# pot.net
KiCad netlist of a schematic drawn in EAGLE
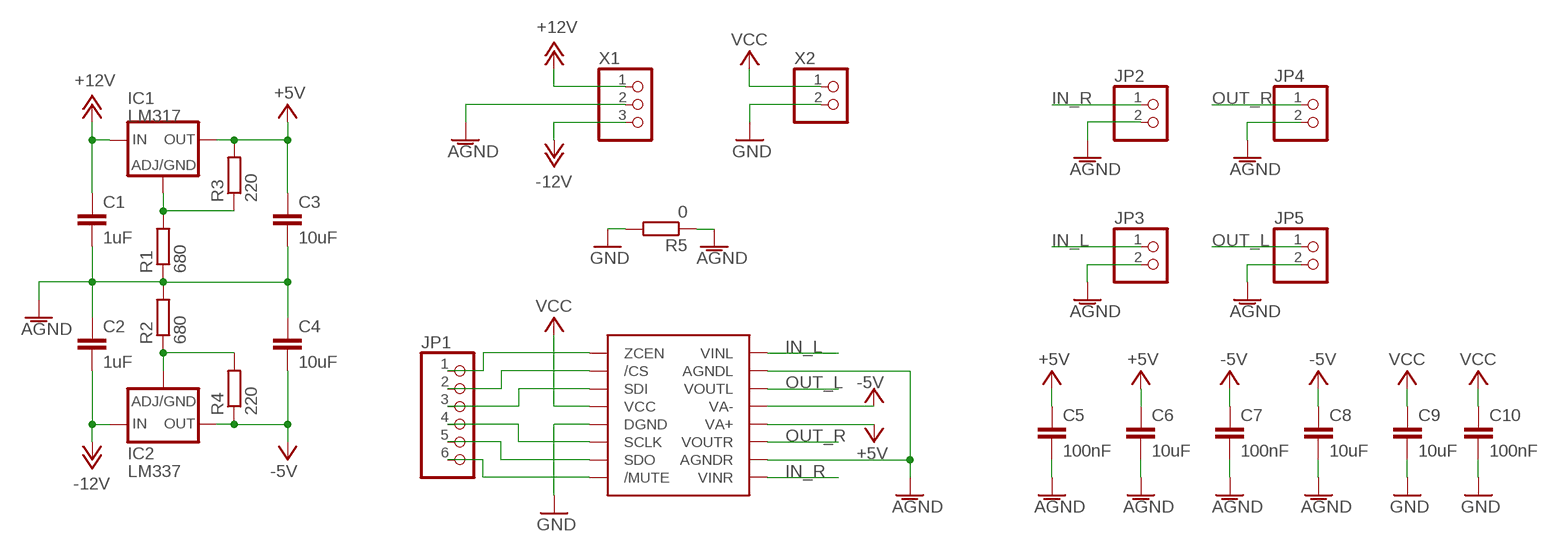
[diagram p0: schematic, sheet 1]

(export (version "E")
  (design (tool "Eeschema 10.0.6"))
  (components
    (comp (ref "C1")
      (value "1uF")
      (footprint "eagle-import:C0805K")
      (libsource (lib "eagle-import") (part "C-EUC0805K"))
    )
    (comp (ref "C2")
      (value "1uF")
      (footprint "eagle-import:C0805K")
      (libsource (lib "eagle-import") (part "C-EUC0805K"))
    )
    (comp (ref "C3")
      (value "10uF")
      (footprint "eagle-import:C0805K")
      (libsource (lib "eagle-import") (part "C-EUC0805K"))
    )
    (comp (ref "C4")
      (value "10uF")
      (footprint "eagle-import:C0805K")
      (libsource (lib "eagle-import") (part "C-EUC0805K"))
    )
    (comp (ref "C5")
      (value "100nF")
      (footprint "eagle-import:C0805K")
      (libsource (lib "eagle-import") (part "C-EUC0805K"))
    )
    (comp (ref "C6")
      (value "10uF")
      (footprint "eagle-import:C0805K")
      (libsource (lib "eagle-import") (part "C-EUC0805K"))
    )
    (comp (ref "C7")
      (value "100nF")
      (footprint "eagle-import:C0805K")
      (libsource (lib "eagle-import") (part "C-EUC0805K"))
    )
    (comp (ref "C8")
      (value "10uF")
      (footprint "eagle-import:C0805K")
      (libsource (lib "eagle-import") (part "C-EUC0805K"))
    )
    (comp (ref "C9")
      (value "10uF")
      (footprint "eagle-import:C0805K")
      (libsource (lib "eagle-import") (part "C-EUC0805K"))
    )
    (comp (ref "C10")
      (value "100nF")
      (footprint "eagle-import:C0805K")
      (libsource (lib "eagle-import") (part "C-EUC0805K"))
    )
    (comp (ref "IC1")
      (value "LM317")
      (footprint "eagle-import:SOT223")
      (libsource (lib "eagle-import") (part "LM317"))
    )
    (comp (ref "IC2")
      (value "LM337")
      (footprint "eagle-import:SOT223")
      (libsource (lib "eagle-import") (part "LM337"))
    )
    (comp (ref "JP1")
      (value "PINHD-1X6")
      (footprint "eagle-import:1X06")
      (libsource (lib "eagle-import") (part "PINHD-1X6"))
    )
    (comp (ref "JP2")
      (value "PINHD-1X2")
      (footprint "eagle-import:1X02")
      (libsource (lib "eagle-import") (part "PINHD-1X2"))
    )
    (comp (ref "JP3")
      (value "PINHD-1X2")
      (footprint "eagle-import:1X02")
      (libsource (lib "eagle-import") (part "PINHD-1X2"))
    )
    (comp (ref "JP4")
      (value "PINHD-1X2")
      (footprint "eagle-import:1X02")
      (libsource (lib "eagle-import") (part "PINHD-1X2"))
    )
    (comp (ref "JP5")
      (value "PINHD-1X2")
      (footprint "eagle-import:1X02")
      (libsource (lib "eagle-import") (part "PINHD-1X2"))
    )
    (comp (ref "R1")
      (value "680")
      (footprint "eagle-import:R0805")
      (libsource (lib "eagle-import") (part "R-EU_"))
    )
    (comp (ref "R2")
      (value "680")
      (footprint "eagle-import:R0805")
      (libsource (lib "eagle-import") (part "R-EU_"))
    )
    (comp (ref "R3")
      (value "220")
      (footprint "eagle-import:R0805")
      (libsource (lib "eagle-import") (part "R-EU_"))
    )
    (comp (ref "R4")
      (value "220")
      (footprint "eagle-import:R0805")
      (libsource (lib "eagle-import") (part "R-EU_"))
    )
    (comp (ref "R5")
      (value "0")
      (footprint "eagle-import:R0805")
      (libsource (lib "eagle-import") (part "R-EU_"))
    )
    (comp (ref "U1")
      (value "PGA2311")
      (footprint "eagle-import:SO16W")
      (libsource (lib "eagle-import") (part "PGA2311"))
    )
    (comp (ref "X1")
      (value "22-23-2031")
      (footprint "eagle-import:22-23-2031")
      (libsource (lib "eagle-import") (part "22-23-2031"))
    )
    (comp (ref "X2")
      (value "22-23-2021")
      (footprint "eagle-import:22-23-2021")
      (libsource (lib "eagle-import") (part "22-23-2021"))
    )
  )
  (nets
    (net (code "1") (name "+5V") (class "Default")
      (node (ref "C3") (pin "1") (pinfunction "1_1") (pintype "passive"))
      (node (ref "C5") (pin "1") (pinfunction "1_1") (pintype "passive"))
      (node (ref "C6") (pin "1") (pinfunction "1_1") (pintype "passive"))
      (node (ref "IC1") (pin "2") (pinfunction "OUT_2") (pintype "passive"))
      (node (ref "IC1") (pin "4") (pinfunction "OUT_4") (pintype "passive"))
      (node (ref "R3") (pin "2") (pinfunction "2_2") (pintype "passive"))
      (node (ref "U1") (pin "12") (pinfunction "VA+_12") (pintype "bidirectional"))
    )
    (net (code "2") (name "+12V") (class "Default")
      (node (ref "C1") (pin "1") (pinfunction "1_1") (pintype "passive"))
      (node (ref "IC1") (pin "3") (pinfunction "IN_3") (pintype "input"))
      (node (ref "X1") (pin "1") (pinfunction "1_1") (pintype "passive"))
    )
    (net (code "3") (name "-5V") (class "Default")
      (node (ref "C4") (pin "1") (pinfunction "1_1") (pintype "passive"))
      (node (ref "C7") (pin "1") (pinfunction "1_1") (pintype "passive"))
      (node (ref "C8") (pin "1") (pinfunction "1_1") (pintype "passive"))
      (node (ref "IC2") (pin "3") (pinfunction "OUT_3") (pintype "passive"))
      (node (ref "R4") (pin "1") (pinfunction "1_1") (pintype "passive"))
      (node (ref "U1") (pin "13") (pinfunction "VA-_13") (pintype "bidirectional"))
    )
    (net (code "4") (name "-12V") (class "Default")
      (node (ref "C2") (pin "1") (pinfunction "1_1") (pintype "passive"))
      (node (ref "IC2") (pin "2") (pinfunction "IN_2") (pintype "input"))
      (node (ref "IC2") (pin "4") (pinfunction "IN_4") (pintype "input"))
      (node (ref "X1") (pin "3") (pinfunction "3_3") (pintype "passive"))
    )
    (net (code "5") (name "/IN_L") (class "Default")
      (node (ref "JP3") (pin "1") (pinfunction "1_1") (pintype "passive"))
      (node (ref "U1") (pin "16") (pinfunction "VINL_16") (pintype "bidirectional"))
    )
    (net (code "6") (name "/IN_R") (class "Default")
      (node (ref "JP2") (pin "1") (pinfunction "1_1") (pintype "passive"))
      (node (ref "U1") (pin "9") (pinfunction "VINR_9") (pintype "bidirectional"))
    )
    (net (code "7") (name "/OUT_L") (class "Default")
      (node (ref "JP5") (pin "1") (pinfunction "1_1") (pintype "passive"))
      (node (ref "U1") (pin "14") (pinfunction "VOUTL_14") (pintype "bidirectional"))
    )
    (net (code "8") (name "/OUT_R") (class "Default")
      (node (ref "JP4") (pin "1") (pinfunction "1_1") (pintype "passive"))
      (node (ref "U1") (pin "11") (pinfunction "VOUTR_11") (pintype "bidirectional"))
    )
    (net (code "9") (name "AGND") (class "Default")
      (node (ref "C1") (pin "2") (pinfunction "2_2") (pintype "passive"))
      (node (ref "C2") (pin "2") (pinfunction "2_2") (pintype "passive"))
      (node (ref "C3") (pin "2") (pinfunction "2_2") (pintype "passive"))
      (node (ref "C4") (pin "2") (pinfunction "2_2") (pintype "passive"))
      (node (ref "C5") (pin "2") (pinfunction "2_2") (pintype "passive"))
      (node (ref "C6") (pin "2") (pinfunction "2_2") (pintype "passive"))
      (node (ref "C7") (pin "2") (pinfunction "2_2") (pintype "passive"))
      (node (ref "C8") (pin "2") (pinfunction "2_2") (pintype "passive"))
      (node (ref "JP2") (pin "2") (pinfunction "2_2") (pintype "passive"))
      (node (ref "JP3") (pin "2") (pinfunction "2_2") (pintype "passive"))
      (node (ref "JP4") (pin "2") (pinfunction "2_2") (pintype "passive"))
      (node (ref "JP5") (pin "2") (pinfunction "2_2") (pintype "passive"))
      (node (ref "R1") (pin "1") (pinfunction "1_1") (pintype "passive"))
      (node (ref "R2") (pin "2") (pinfunction "2_2") (pintype "passive"))
      (node (ref "R5") (pin "1") (pinfunction "1_1") (pintype "passive"))
      (node (ref "U1") (pin "10") (pinfunction "AGNDR_10") (pintype "bidirectional"))
      (node (ref "U1") (pin "15") (pinfunction "AGNDL_15") (pintype "bidirectional"))
      (node (ref "X1") (pin "2") (pinfunction "2_2") (pintype "passive"))
    )
    (net (code "10") (name "GND") (class "Default")
      (node (ref "C10") (pin "2") (pinfunction "2_2") (pintype "passive"))
      (node (ref "C9") (pin "2") (pinfunction "2_2") (pintype "passive"))
      (node (ref "R5") (pin "2") (pinfunction "2_2") (pintype "passive"))
      (node (ref "U1") (pin "5") (pinfunction "DGND_5") (pintype "bidirectional"))
      (node (ref "X2") (pin "2") (pinfunction "2_2") (pintype "passive"))
    )
    (net (code "11") (name "Net-(IC1-ADJ)") (class "Default")
      (node (ref "IC1") (pin "1") (pinfunction "ADJ_1") (pintype "input"))
      (node (ref "R1") (pin "2") (pinfunction "2_2") (pintype "passive"))
      (node (ref "R3") (pin "1") (pinfunction "1_1") (pintype "passive"))
    )
    (net (code "12") (name "Net-(IC2-ADJ)") (class "Default")
      (node (ref "IC2") (pin "1") (pinfunction "ADJ_1") (pintype "input"))
      (node (ref "R2") (pin "1") (pinfunction "1_1") (pintype "passive"))
      (node (ref "R4") (pin "2") (pinfunction "2_2") (pintype "passive"))
    )
    (net (code "13") (name "Net-(U1-SCLK)") (class "Default")
      (node (ref "JP1") (pin "4") (pinfunction "4_4") (pintype "passive"))
      (node (ref "U1") (pin "6") (pinfunction "SCLK_6") (pintype "bidirectional"))
    )
    (net (code "14") (name "Net-(U1-SDI)") (class "Default")
      (node (ref "JP1") (pin "3") (pinfunction "3_3") (pintype "passive"))
      (node (ref "U1") (pin "3") (pinfunction "SDI_3") (pintype "bidirectional"))
    )
    (net (code "15") (name "Net-(U1-SDO)") (class "Default")
      (node (ref "JP1") (pin "5") (pinfunction "5_5") (pintype "passive"))
      (node (ref "U1") (pin "7") (pinfunction "SDO_7") (pintype "bidirectional"))
    )
    (net (code "16") (name "Net-(U1-ZCEN)") (class "Default")
      (node (ref "JP1") (pin "1") (pinfunction "1_1") (pintype "passive"))
      (node (ref "U1") (pin "1") (pinfunction "ZCEN_1") (pintype "bidirectional"))
    )
    (net (code "17") (name "Net-(U1-{slash}CS)") (class "Default")
      (node (ref "JP1") (pin "2") (pinfunction "2_2") (pintype "passive"))
      (node (ref "U1") (pin "2") (pinfunction "/CS_2") (pintype "bidirectional"))
    )
    (net (code "18") (name "Net-(U1-{slash}MUTE)") (class "Default")
      (node (ref "JP1") (pin "6") (pinfunction "6_6") (pintype "passive"))
      (node (ref "U1") (pin "8") (pinfunction "/MUTE_8") (pintype "bidirectional"))
    )
    (net (code "19") (name "VCC") (class "Default")
      (node (ref "C10") (pin "1") (pinfunction "1_1") (pintype "passive"))
      (node (ref "C9") (pin "1") (pinfunction "1_1") (pintype "passive"))
      (node (ref "U1") (pin "4") (pinfunction "VCC_4") (pintype "bidirectional"))
      (node (ref "X2") (pin "1") (pinfunction "1_1") (pintype "passive"))
    )
  )
)
